# Interfaces.net
KiCad netlist of a schematic drawn in Altium Designer
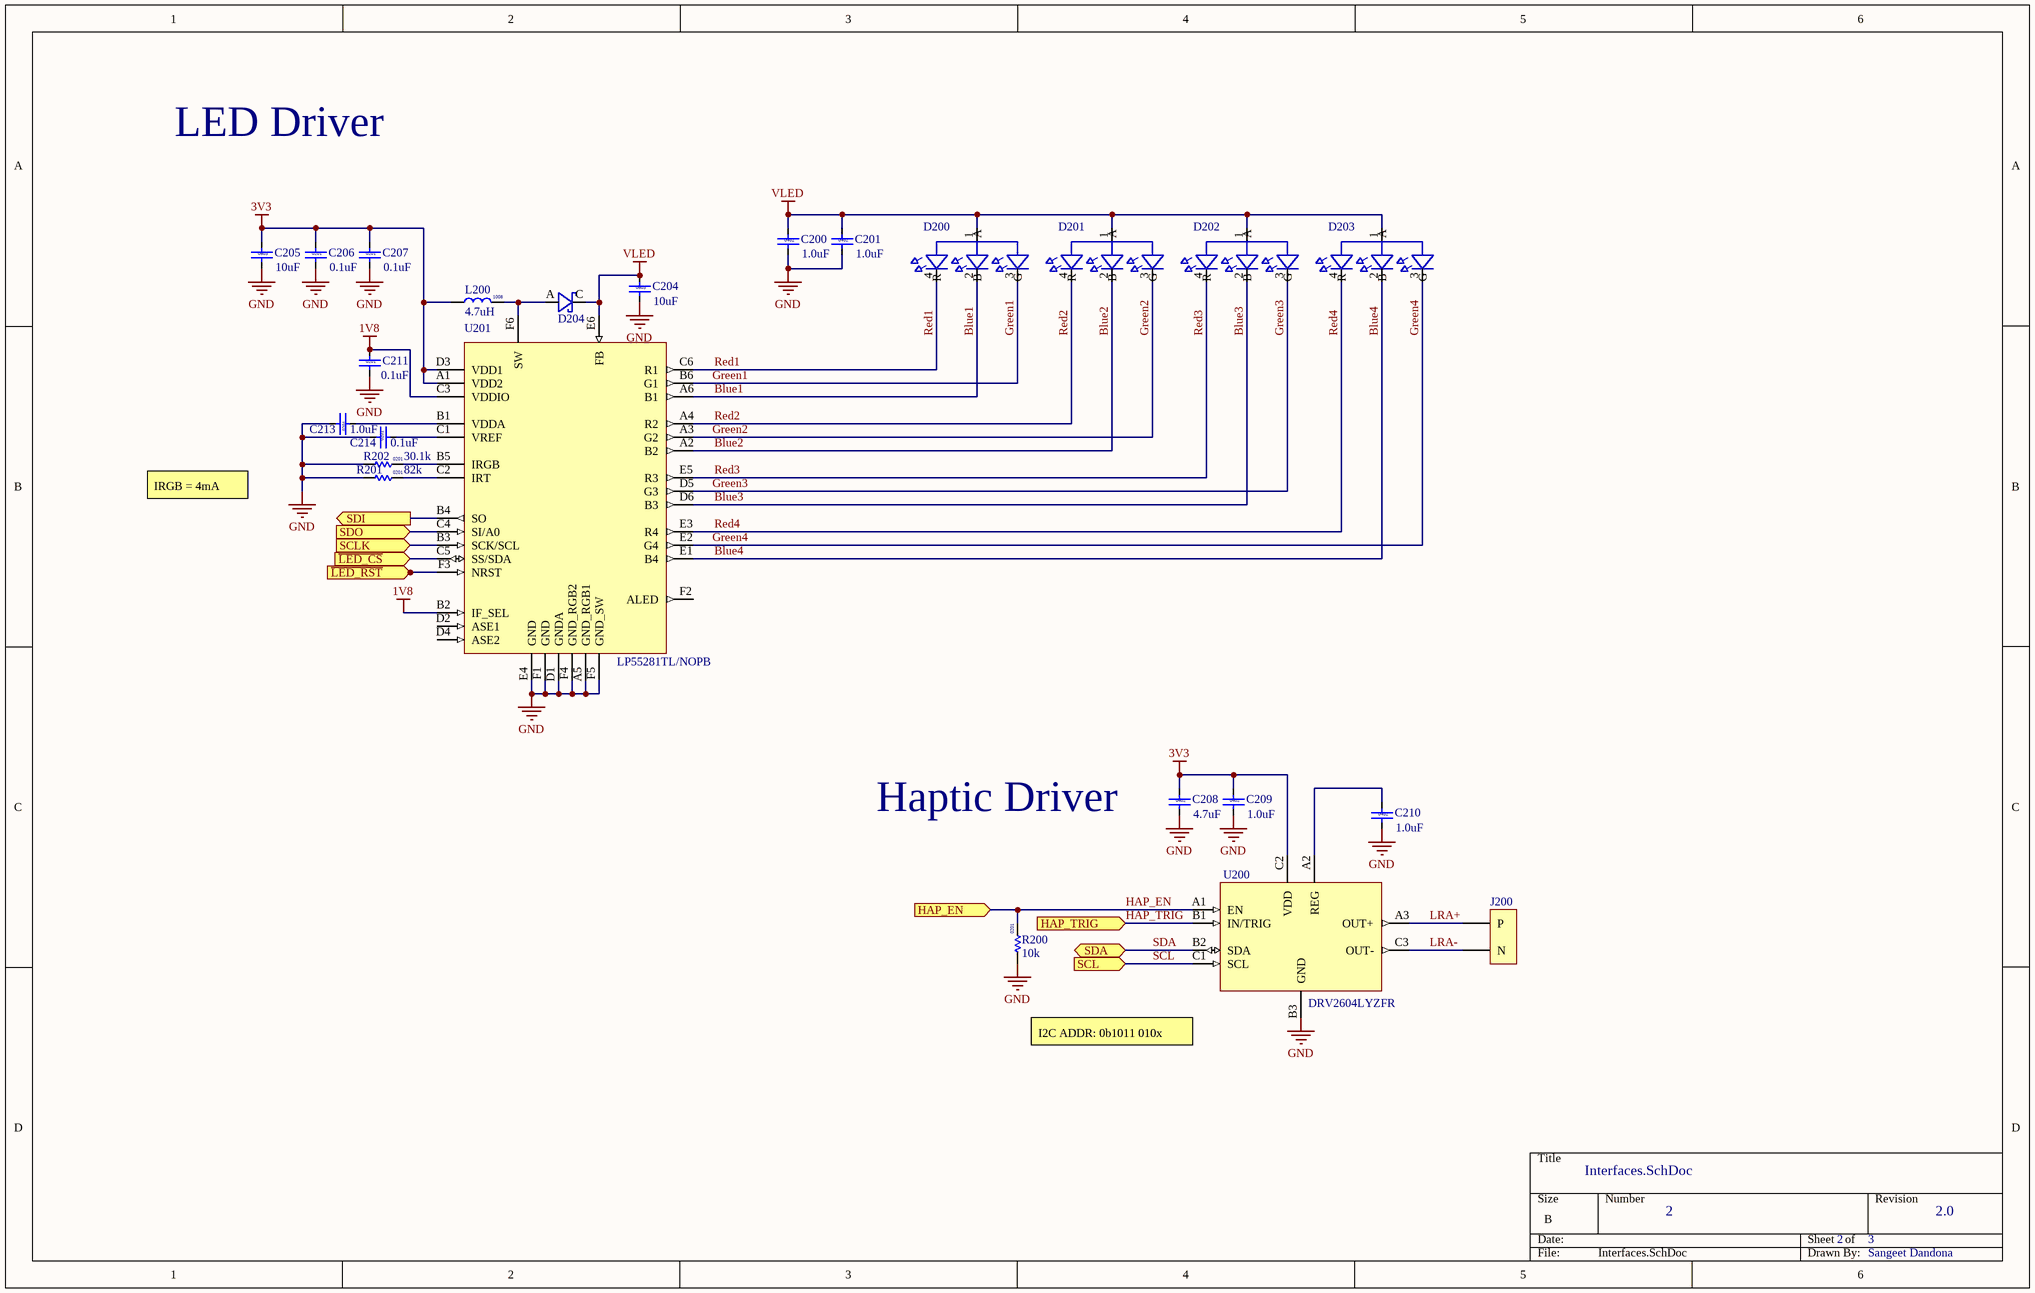
[diagram p0: Interfaces.SchDoc]

(export (version "E")
  (design (tool "Eeschema 10.0.6"))
  (components
    (comp (ref "C200")
      (value "1.0uF")
      (footprint "Cap 0402 HD")
      (description "CAP CER 1UF 10V 10% X5R 0402")
      (fields (field (name "SIZE") "0402") (field (name "MF") "Murata Electronics North America"))
      (libsource (lib "Rigado_AltiumLib") (part "Cap Chip"))
    )
    (comp (ref "C201")
      (value "1.0uF")
      (footprint "Cap 0402 HD")
      (description "CAP CER 1UF 10V 10% X5R 0402")
      (fields (field (name "SIZE") "0402") (field (name "MF") "Murata Electronics North America"))
      (libsource (lib "Rigado_AltiumLib") (part "Cap Chip"))
    )
    (comp (ref "C204")
      (value "10uF")
      (footprint "Cap 0603")
      (description "CAP CER 10UF 10V 20% X5R 0603")
      (fields (field (name "SIZE") "0603") (field (name "MF") "TDK Corporation"))
      (libsource (lib "Rigado_AltiumLib") (part "Cap Chip"))
    )
    (comp (ref "C205")
      (value "10uF")
      (footprint "Cap 0603")
      (description "CAP CER 10UF 10V 20% X5R 0603")
      (fields (field (name "SIZE") "0603") (field (name "MF") "TDK Corporation"))
      (libsource (lib "Rigado_AltiumLib") (part "Cap Chip"))
    )
    (comp (ref "C206")
      (value "0.1uF")
      (footprint "Cap 0201 HD")
      (description "CAP CER 0.1UF 6.3V 10% X5R 0201")
      (fields (field (name "SIZE") "0201") (field (name "MF") "Murata Electronics North America"))
      (libsource (lib "Rigado_AltiumLib") (part "Cap Chip"))
    )
    (comp (ref "C207")
      (value "0.1uF")
      (footprint "Cap 0201 HD")
      (description "CAP CER 0.1UF 6.3V 10% X5R 0201")
      (fields (field (name "SIZE") "0201") (field (name "MF") "Murata Electronics North America"))
      (libsource (lib "Rigado_AltiumLib") (part "Cap Chip"))
    )
    (comp (ref "C208")
      (value "4.7uF")
      (footprint "Cap 0402 HD")
      (description "CAP CER 4.7UF 10V 20% X5R 0402")
      (fields (field (name "SIZE") "0402") (field (name "MF") "Samsung Electro-Mechanics America, Inc."))
      (libsource (lib "Rigado_AltiumLib") (part "Cap Chip"))
    )
    (comp (ref "C209")
      (value "1.0uF")
      (footprint "Cap 0402 HD")
      (description "CAP CER 1UF 10V 10% X5R 0402")
      (fields (field (name "SIZE") "0402") (field (name "MF") "Murata Electronics North America"))
      (libsource (lib "Rigado_AltiumLib") (part "Cap Chip"))
    )
    (comp (ref "C210")
      (value "1.0uF")
      (footprint "Cap 0402 HD")
      (description "CAP CER 1UF 10V 10% X5R 0402")
      (fields (field (name "SIZE") "0402") (field (name "MF") "Murata Electronics North America"))
      (libsource (lib "Rigado_AltiumLib") (part "Cap Chip"))
    )
    (comp (ref "C211")
      (value "0.1uF")
      (footprint "Cap 0201 HD")
      (description "CAP CER 0.1UF 6.3V 10% X5R 0201")
      (fields (field (name "SIZE") "0201") (field (name "MF") "Murata Electronics North America"))
      (libsource (lib "Rigado_AltiumLib") (part "Cap Chip"))
    )
    (comp (ref "C213")
      (value "1.0uF")
      (footprint "Cap 0201 HD")
      (description "CAP CER 1UF 6.3V 20% X5R 0201")
      (fields (field (name "SIZE") "0201") (field (name "MF") "Samsung Electro-Mechanics America, Inc."))
      (libsource (lib "Rigado_AltiumLib") (part "Cap Chip"))
    )
    (comp (ref "C214")
      (value "0.1uF")
      (footprint "Cap 0201 HD")
      (description "CAP CER 0.1UF 6.3V 10% X5R 0201")
      (fields (field (name "SIZE") "0201") (field (name "MF") "Murata Electronics North America"))
      (libsource (lib "Rigado_AltiumLib") (part "Cap Chip"))
    )
    (comp (ref "D200")
      (value "~")
      (footprint "4-PLCC")
      (description "LED RGB 3-IN-1 SMD 4PLCC")
      (fields (field (name "MF") "Cree Inc."))
      (libsource (lib "Rigado_AltiumLib") (part "LED_RGB_CA_2"))
    )
    (comp (ref "D201")
      (value "~")
      (footprint "4-PLCC")
      (description "LED RGB 3-IN-1 SMD 4PLCC")
      (fields (field (name "MF") "Cree Inc."))
      (libsource (lib "Rigado_AltiumLib") (part "LED_RGB_CA_2"))
    )
    (comp (ref "D202")
      (value "~")
      (footprint "4-PLCC")
      (description "LED RGB 3-IN-1 SMD 4PLCC")
      (fields (field (name "MF") "Cree Inc."))
      (libsource (lib "Rigado_AltiumLib") (part "LED_RGB_CA_2"))
    )
    (comp (ref "D203")
      (value "~")
      (footprint "4-PLCC")
      (description "LED RGB 3-IN-1 SMD 4PLCC")
      (fields (field (name "MF") "Cree Inc."))
      (libsource (lib "Rigado_AltiumLib") (part "LED_RGB_CA_2"))
    )
    (comp (ref "D204")
      (value "~")
      (footprint "SOD-123F_U")
      (description "DIODE SCHOTTKY 20V 1A SOD123FL")
      (fields (field (name "MF") "ON Semiconductor"))
      (libsource (lib "LOCAL_Rigado_AltiumLib") (part "Diode_Schottky"))
    )
    (comp (ref "J200")
      (value "MOLEX_RA_CONN")
      (footprint "MOLEX_RA_CONN")
      (description "CONN HEADER 2POS 1.25MM R/A SMD")
      (fields (field (name "MF") "Molex, LLC"))
      (libsource (lib "JDB-001") (part "MOLEX_RA_CONN"))
    )
    (comp (ref "L200")
      (value "4.7uH")
      (footprint "IND 1008")
      (description "FIXED IND 4.7UH 1A 250 MOHM SMD")
      (fields (field (name "SIZE") "1008") (field (name "MF") "Samsung Electro-Mechanics America, Inc."))
      (libsource (lib "Rigado_AltiumLib") (part "Ind sm"))
    )
    (comp (ref "R200")
      (value "10k")
      (footprint "RES 0201 HD")
      (description "RES SMD 10K OHM 5% 1/20W 0201")
      (fields (field (name "SIZE") "0201") (field (name "MF") "Rohm Semiconductor"))
      (libsource (lib "Rigado_AltiumLib") (part "Res sm"))
    )
    (comp (ref "R201")
      (value "82k")
      (footprint "RES 0201 HD")
      (description "RES SMD 82K OHM 1% 1/20W 0201")
      (fields (field (name "SIZE") "0201") (field (name "MF") "Panasonic Electronic Components"))
      (libsource (lib "Rigado_AltiumLib") (part "Res sm"))
    )
    (comp (ref "R202")
      (value "30.1k")
      (footprint "RES 0201 HD")
      (description "RES SMD 30.1K OHM 1% 1/20W 0201")
      (fields (field (name "SIZE") "0201") (field (name "MF") "Panasonic Electronic Components"))
      (libsource (lib "Rigado_AltiumLib") (part "Res sm"))
    )
    (comp (ref "U200")
      (value "~")
      (footprint "BGA0.5P3x3-9Pin")
      (description "IC ERM/LRA HAPTIC DRIVER 9DSBGA")
      (fields (field (name "MF") "Texas Instruments") (field (name "MFPN") "DRV2604LYZFR"))
      (libsource (lib "JDB-001") (part "DRV2604L"))
    )
    (comp (ref "U201")
      (value "~")
      (footprint "BGA0.5P6x6-36Pin")
      (description "IC LED DRIVER RGLTR DIM 36USMD")
      (fields (field (name "MF") "Texas Instruments") (field (name "MFPN") "LP55281TL/NOPB"))
      (libsource (lib "Rigado_AltiumLib") (part "LP55281"))
    )
  )
  (nets
    (net (code "1") (name "/Blue1") (class "Default")
      (node (ref "D200") (pin "2") (pinfunction "B_2") (pintype "passive"))
      (node (ref "U201") (pin "A6") (pinfunction "B1_A6") (pintype "output"))
    )
    (net (code "2") (name "/Blue2") (class "Default")
      (node (ref "D201") (pin "2") (pinfunction "B_2") (pintype "passive"))
      (node (ref "U201") (pin "A2") (pinfunction "B2_A2") (pintype "output"))
    )
    (net (code "3") (name "/Blue3") (class "Default")
      (node (ref "D202") (pin "2") (pinfunction "B_2") (pintype "passive"))
      (node (ref "U201") (pin "D6") (pinfunction "B3_D6") (pintype "output"))
    )
    (net (code "4") (name "/Blue4") (class "Default")
      (node (ref "D203") (pin "2") (pinfunction "B_2") (pintype "passive"))
      (node (ref "U201") (pin "E1") (pinfunction "B4_E1") (pintype "output"))
    )
    (net (code "5") (name "/Green1") (class "Default")
      (node (ref "D200") (pin "3") (pinfunction "G_3") (pintype "passive"))
      (node (ref "U201") (pin "B6") (pinfunction "G1_B6") (pintype "output"))
    )
    (net (code "6") (name "/Green2") (class "Default")
      (node (ref "D201") (pin "3") (pinfunction "G_3") (pintype "passive"))
      (node (ref "U201") (pin "A3") (pinfunction "G2_A3") (pintype "output"))
    )
    (net (code "7") (name "/Green3") (class "Default")
      (node (ref "D202") (pin "3") (pinfunction "G_3") (pintype "passive"))
      (node (ref "U201") (pin "D5") (pinfunction "G3_D5") (pintype "output"))
    )
    (net (code "8") (name "/Green4") (class "Default")
      (node (ref "D203") (pin "3") (pinfunction "G_3") (pintype "passive"))
      (node (ref "U201") (pin "E2") (pinfunction "G4_E2") (pintype "output"))
    )
    (net (code "9") (name "/HAP_EN") (class "Default")
      (node (ref "R200") (pin "2") (pinfunction "2_2") (pintype "passive"))
      (node (ref "U200") (pin "A1") (pinfunction "EN_A1") (pintype "input"))
    )
    (net (code "10") (name "/HAP_TRIG") (class "Default")
      (node (ref "U200") (pin "B1") (pinfunction "IN/TRIG_B1") (pintype "input"))
    )
    (net (code "11") (name "/LED_CS") (class "Default")
      (node (ref "U201") (pin "C5") (pinfunction "SS/SDA_C5") (pintype "bidirectional"))
    )
    (net (code "12") (name "/LED_RST") (class "Default")
      (node (ref "U201") (pin "F3") (pinfunction "NRST_F3") (pintype "input"))
    )
    (net (code "13") (name "/LRA+") (class "Default")
      (node (ref "J200") (pin "1") (pinfunction "P_1") (pintype "passive"))
      (node (ref "U200") (pin "A3") (pinfunction "OUT+_A3") (pintype "output"))
    )
    (net (code "14") (name "/LRA-") (class "Default")
      (node (ref "J200") (pin "2") (pinfunction "N_2") (pintype "passive"))
      (node (ref "U200") (pin "C3") (pinfunction "OUT-_C3") (pintype "output"))
    )
    (net (code "15") (name "/Red1") (class "Default")
      (node (ref "D200") (pin "4") (pinfunction "R_4") (pintype "passive"))
      (node (ref "U201") (pin "C6") (pinfunction "R1_C6") (pintype "output"))
    )
    (net (code "16") (name "/Red2") (class "Default")
      (node (ref "D201") (pin "4") (pinfunction "R_4") (pintype "passive"))
      (node (ref "U201") (pin "A4") (pinfunction "R2_A4") (pintype "output"))
    )
    (net (code "17") (name "/Red3") (class "Default")
      (node (ref "D202") (pin "4") (pinfunction "R_4") (pintype "passive"))
      (node (ref "U201") (pin "E5") (pinfunction "R3_E5") (pintype "output"))
    )
    (net (code "18") (name "/Red4") (class "Default")
      (node (ref "D203") (pin "4") (pinfunction "R_4") (pintype "passive"))
      (node (ref "U201") (pin "E3") (pinfunction "R4_E3") (pintype "output"))
    )
    (net (code "19") (name "/SCL") (class "Default")
      (node (ref "U200") (pin "C1") (pinfunction "SCL_C1") (pintype "input"))
    )
    (net (code "20") (name "/SCLK") (class "Default")
      (node (ref "U201") (pin "B3") (pinfunction "SCK/SCL_B3") (pintype "input"))
    )
    (net (code "21") (name "/SDA") (class "Default")
      (node (ref "U200") (pin "B2") (pinfunction "SDA_B2") (pintype "bidirectional"))
    )
    (net (code "22") (name "/SDI") (class "Default")
      (node (ref "U201") (pin "B4") (pinfunction "SO_B4") (pintype "output"))
    )
    (net (code "23") (name "/SDO") (class "Default")
      (node (ref "U201") (pin "C4") (pinfunction "SI/A0_C4") (pintype "input"))
    )
    (net (code "24") (name "1V8") (class "Default")
      (node (ref "C211") (pin "1") (pinfunction "1_1") (pintype "passive"))
      (node (ref "U201") (pin "B2") (pinfunction "IF_SEL_B2") (pintype "input"))
      (node (ref "U201") (pin "C3") (pinfunction "VDDIO_C3") (pintype "power_in"))
    )
    (net (code "25") (name "3V3") (class "Default")
      (node (ref "C205") (pin "1") (pinfunction "1_1") (pintype "passive"))
      (node (ref "C206") (pin "1") (pinfunction "1_1") (pintype "passive"))
      (node (ref "C207") (pin "1") (pinfunction "1_1") (pintype "passive"))
      (node (ref "C208") (pin "1") (pinfunction "1_1") (pintype "passive"))
      (node (ref "C209") (pin "1") (pinfunction "1_1") (pintype "passive"))
      (node (ref "L200") (pin "1") (pinfunction "1_1") (pintype "passive"))
      (node (ref "U200") (pin "C2") (pinfunction "VDD_C2") (pintype "power_in"))
      (node (ref "U201") (pin "A1") (pinfunction "VDD2_A1") (pintype "power_in"))
      (node (ref "U201") (pin "D3") (pinfunction "VDD1_D3") (pintype "power_in"))
    )
    (net (code "26") (name "GND") (class "Default")
      (node (ref "C200") (pin "2") (pinfunction "2_2") (pintype "passive"))
      (node (ref "C201") (pin "2") (pinfunction "2_2") (pintype "passive"))
      (node (ref "C204") (pin "2") (pinfunction "2_2") (pintype "passive"))
      (node (ref "C205") (pin "2") (pinfunction "2_2") (pintype "passive"))
      (node (ref "C206") (pin "2") (pinfunction "2_2") (pintype "passive"))
      (node (ref "C207") (pin "2") (pinfunction "2_2") (pintype "passive"))
      (node (ref "C208") (pin "2") (pinfunction "2_2") (pintype "passive"))
      (node (ref "C209") (pin "2") (pinfunction "2_2") (pintype "passive"))
      (node (ref "C210") (pin "2") (pinfunction "2_2") (pintype "passive"))
      (node (ref "C211") (pin "2") (pinfunction "2_2") (pintype "passive"))
      (node (ref "C213") (pin "2") (pinfunction "2_2") (pintype "passive"))
      (node (ref "C214") (pin "1") (pinfunction "1_1") (pintype "passive"))
      (node (ref "R200") (pin "1") (pinfunction "1_1") (pintype "passive"))
      (node (ref "R201") (pin "1") (pinfunction "1_1") (pintype "passive"))
      (node (ref "R202") (pin "1") (pinfunction "1_1") (pintype "passive"))
      (node (ref "U200") (pin "B3") (pinfunction "GND_B3") (pintype "power_in"))
      (node (ref "U201") (pin "A5") (pinfunction "GND_RGB1_A5") (pintype "power_in"))
      (node (ref "U201") (pin "D1") (pinfunction "GNDA_D1") (pintype "power_in"))
      (node (ref "U201") (pin "E4") (pinfunction "GND_E4") (pintype "power_in"))
      (node (ref "U201") (pin "F1") (pinfunction "GND_F1") (pintype "power_in"))
      (node (ref "U201") (pin "F4") (pinfunction "GND_RGB2_F4") (pintype "power_in"))
      (node (ref "U201") (pin "F5") (pinfunction "GND_SW_F5") (pintype "power_in"))
    )
    (net (code "27") (name "Net-(U200-REG)") (class "Default")
      (node (ref "C210") (pin "1") (pinfunction "1_1") (pintype "passive"))
      (node (ref "U200") (pin "A2") (pinfunction "REG_A2") (pintype "power_in"))
    )
    (net (code "28") (name "Net-(U201-IRGB)") (class "Default")
      (node (ref "R202") (pin "2") (pinfunction "2_2") (pintype "passive"))
      (node (ref "U201") (pin "B5") (pinfunction "IRGB_B5") (pintype "passive"))
    )
    (net (code "29") (name "Net-(U201-IRT)") (class "Default")
      (node (ref "R201") (pin "2") (pinfunction "2_2") (pintype "passive"))
      (node (ref "U201") (pin "C2") (pinfunction "IRT_C2") (pintype "passive"))
    )
    (net (code "30") (name "Net-(U201-SW)") (class "Default")
      (node (ref "D204") (pin "A") (pintype "passive"))
      (node (ref "L200") (pin "2") (pinfunction "2_2") (pintype "passive"))
      (node (ref "U201") (pin "F6") (pinfunction "SW_F6") (pintype "power_in"))
    )
    (net (code "31") (name "Net-(U201-VDDA)") (class "Default")
      (node (ref "C213") (pin "1") (pinfunction "1_1") (pintype "passive"))
      (node (ref "U201") (pin "B1") (pinfunction "VDDA_B1") (pintype "power_in"))
    )
    (net (code "32") (name "Net-(U201-VREF)") (class "Default")
      (node (ref "C214") (pin "2") (pinfunction "2_2") (pintype "passive"))
      (node (ref "U201") (pin "C1") (pinfunction "VREF_C1") (pintype "passive"))
    )
    (net (code "33") (name "VLED") (class "Default")
      (node (ref "C200") (pin "1") (pinfunction "1_1") (pintype "passive"))
      (node (ref "C201") (pin "1") (pinfunction "1_1") (pintype "passive"))
      (node (ref "C204") (pin "1") (pinfunction "1_1") (pintype "passive"))
      (node (ref "D200") (pin "1") (pinfunction "A_1") (pintype "passive"))
      (node (ref "D201") (pin "1") (pinfunction "A_1") (pintype "passive"))
      (node (ref "D202") (pin "1") (pinfunction "A_1") (pintype "passive"))
      (node (ref "D203") (pin "1") (pinfunction "A_1") (pintype "passive"))
      (node (ref "D204") (pin "C") (pintype "passive"))
      (node (ref "U201") (pin "E6") (pinfunction "FB_E6") (pintype "input"))
    )
    (net (code "34") (name "unconnected-(U201-ALED-PadF2)") (class "Default")
      (node (ref "U201") (pin "F2") (pinfunction "ALED_F2") (pintype "output"))
    )
    (net (code "35") (name "unconnected-(U201-ASE1-PadD2)") (class "Default")
      (node (ref "U201") (pin "D2") (pinfunction "ASE1_D2") (pintype "input"))
    )
    (net (code "36") (name "unconnected-(U201-ASE2-PadD4)") (class "Default")
      (node (ref "U201") (pin "D4") (pinfunction "ASE2_D4") (pintype "input"))
    )
  )
)
